# Pyr0-Piezo-Standalone_3_0_0.net
KiCad netlist of a schematic drawn in EAGLE
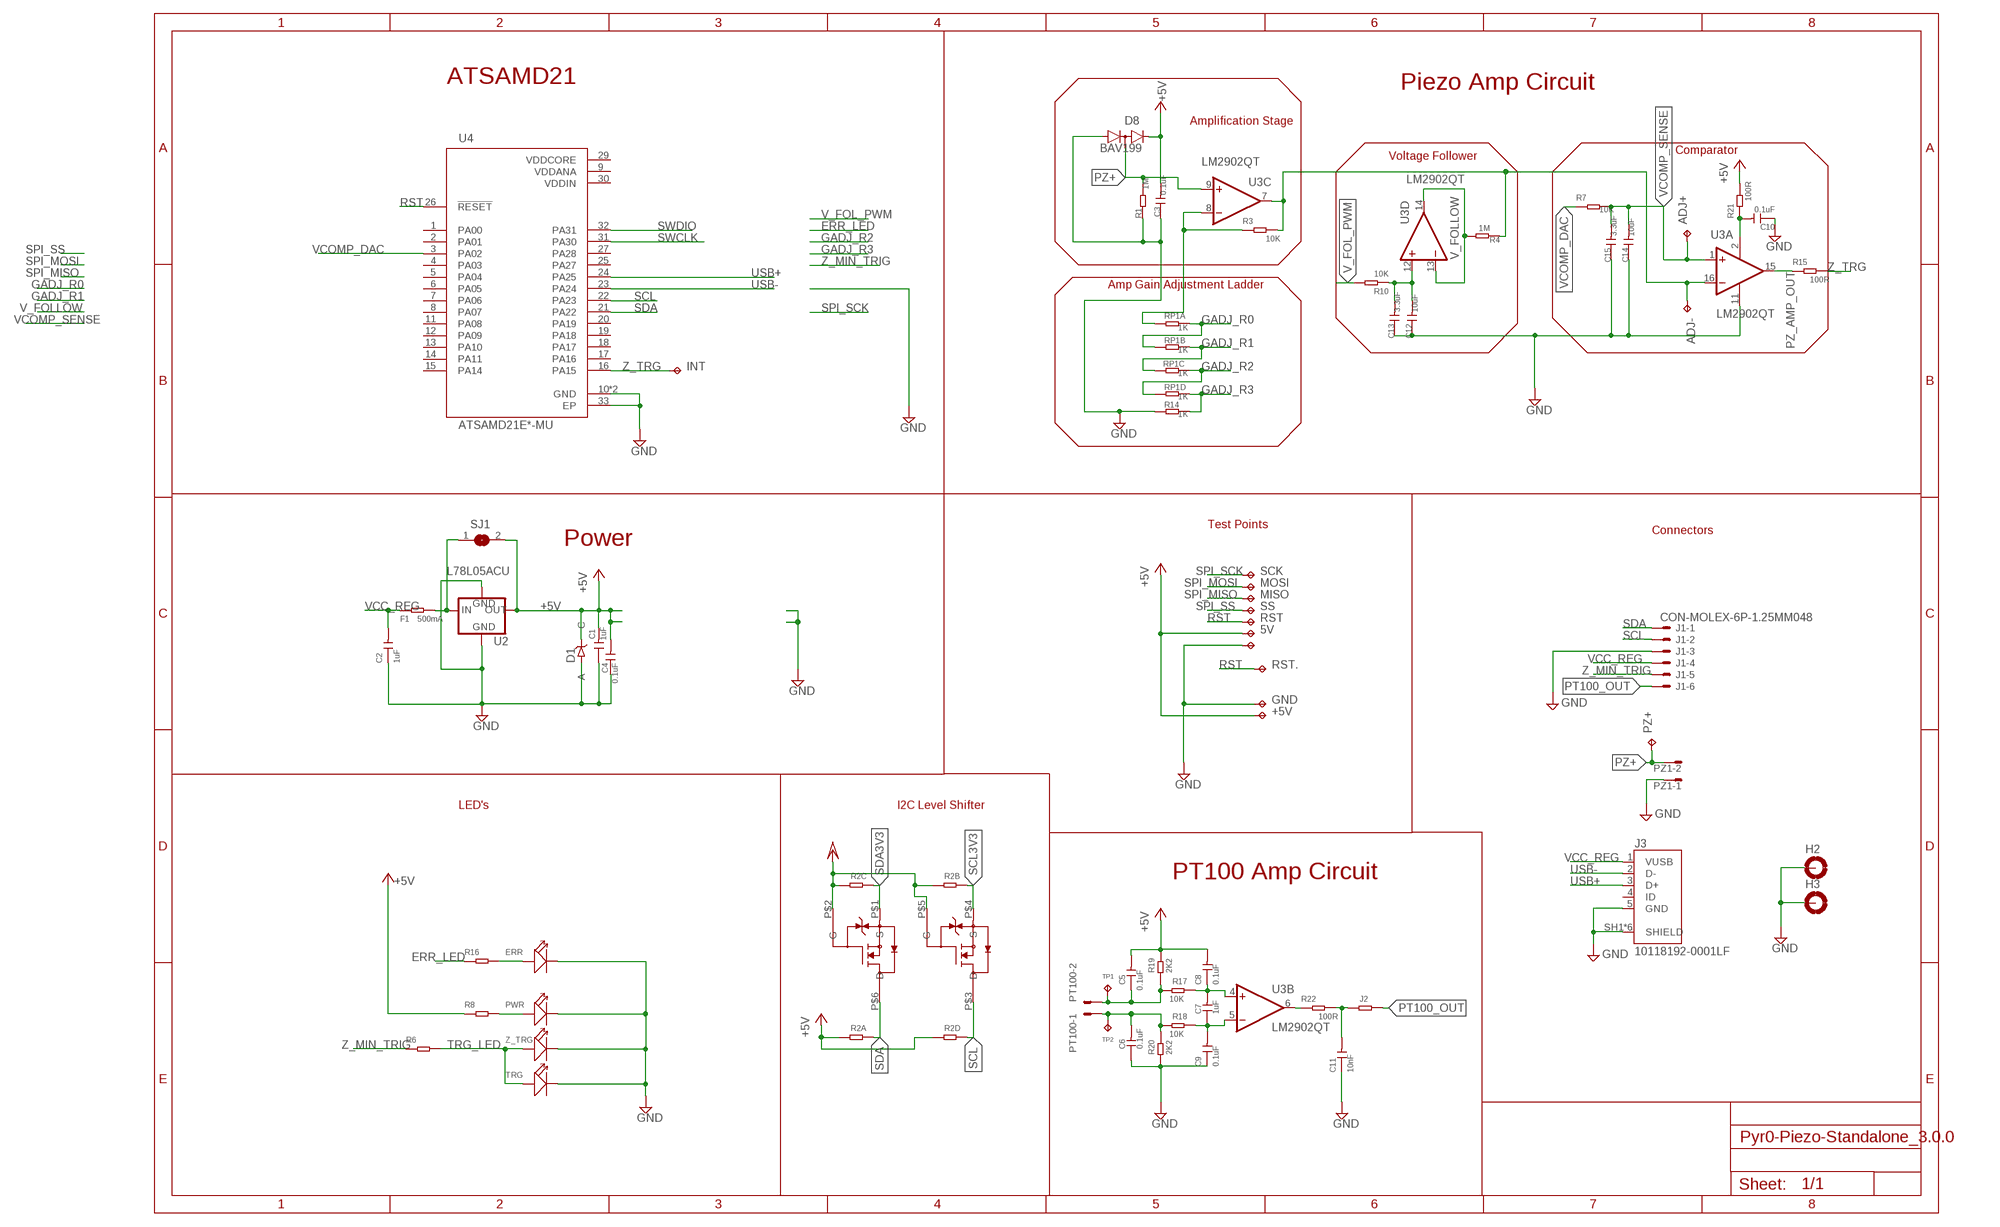
[diagram p0: schematic, sheet 1]

(export (version "E")
  (design (tool "Eeschema 10.0.6"))
  (components
    (comp (ref "+5V")
      (value "TPTP13SQ")
      (footprint "eagle-import:TP13SQ")
      (libsource (lib "eagle-import") (part "testpad_385_TPTP13SQ"))
    )
    (comp (ref "5V")
      (value "TPTP13SQ")
      (footprint "eagle-import:TP13SQ")
      (libsource (lib "eagle-import") (part "TPTP13SQ"))
    )
    (comp (ref "ADJ+")
      (value "TPTP13SQ")
      (footprint "eagle-import:TP13SQ")
      (libsource (lib "eagle-import") (part "TPTP13SQ"))
    )
    (comp (ref "ADJ-")
      (value "TPTP13SQ")
      (footprint "eagle-import:TP13SQ")
      (libsource (lib "eagle-import") (part "TPTP13SQ"))
    )
    (comp (ref "C1")
      (value "1uF")
      (footprint "eagle-import:CAPC1609X80")
      (libsource (lib "eagle-import") (part "SEEED-CAPACITOR_CERAMIC-10UF-25V-10%-X5R(0805)CAP_0603_GEN"))
    )
    (comp (ref "C2")
      (value "1uF")
      (footprint "eagle-import:CAPC1609X80")
      (libsource (lib "eagle-import") (part "SEEED-CAPACITOR_CERAMIC-10UF-25V-10%-X5R(0805)CAP_0603_GEN"))
    )
    (comp (ref "C3")
      (value "0.1uF")
      (footprint "eagle-import:CAPC1005X50")
      (libsource (lib "eagle-import") (part "CERAMIC-1NF-50V-10%-X7R(0402)CAP_0402"))
    )
    (comp (ref "C4")
      (value "0.1uF")
      (footprint "eagle-import:CAPC1005X50")
      (libsource (lib "eagle-import") (part "CERAMIC-1NF-50V-10%-X7R(0402)CAP_0402"))
    )
    (comp (ref "C5")
      (value "0.1uF")
      (footprint "eagle-import:CAPC1005X50")
      (libsource (lib "eagle-import") (part "CERAMIC-1NF-50V-10%-X7R(0402)CAP_0402"))
    )
    (comp (ref "C6")
      (value "0.1uF")
      (footprint "eagle-import:CAPC1005X50")
      (libsource (lib "eagle-import") (part "CERAMIC-1NF-50V-10%-X7R(0402)CAP_0402"))
    )
    (comp (ref "C7")
      (value "1uF")
      (footprint "eagle-import:CAPC1005X50")
      (libsource (lib "eagle-import") (part "CERAMIC-1NF-50V-10%-X7R(0402)CAP_0402"))
    )
    (comp (ref "C8")
      (value "0.1uF")
      (footprint "eagle-import:CAPC1005X50")
      (libsource (lib "eagle-import") (part "CERAMIC-1NF-50V-10%-X7R(0402)CAP_0402"))
    )
    (comp (ref "C9")
      (value "0.1uF")
      (footprint "eagle-import:CAPC1005X50")
      (libsource (lib "eagle-import") (part "CERAMIC-1NF-50V-10%-X7R(0402)CAP_0402"))
    )
    (comp (ref "C10")
      (value "0.1uF")
      (footprint "eagle-import:CAPC1005X50")
      (libsource (lib "eagle-import") (part "CERAMIC-1NF-50V-10%-X7R(0402)CAP_0402"))
    )
    (comp (ref "C11")
      (value "10nF")
      (footprint "eagle-import:CAPC1005X50")
      (libsource (lib "eagle-import") (part "CERAMIC-1NF-50V-10%-X7R(0402)CAP_0402"))
    )
    (comp (ref "C12")
      (value "10uF")
      (footprint "eagle-import:CAPC1005X50")
      (libsource (lib "eagle-import") (part "CERAMIC-1NF-50V-10%-X7R(0402)CAP_0402"))
    )
    (comp (ref "C13")
      (value "3.3uF")
      (footprint "eagle-import:CAPC1005X50")
      (libsource (lib "eagle-import") (part "CERAMIC-1NF-50V-10%-X7R(0402)CAP_0402"))
    )
    (comp (ref "C14")
      (value "10uF")
      (footprint "eagle-import:CAPC1005X50")
      (libsource (lib "eagle-import") (part "CERAMIC-1NF-50V-10%-X7R(0402)CAP_0402"))
    )
    (comp (ref "C15")
      (value "3.3uF")
      (footprint "eagle-import:CAPC1005X50")
      (libsource (lib "eagle-import") (part "CERAMIC-1NF-50V-10%-X7R(0402)CAP_0402"))
    )
    (comp (ref "D1")
      (value "ZENER_DIODE_PLZ5V1C")
      (footprint "eagle-import:DO-219AC")
      (libsource (lib "eagle-import") (part "ZENER_DIODE_PLZ5V1C"))
    )
    (comp (ref "D8")
      (value "BAV199")
      (footprint "eagle-import:SOT23")
      (libsource (lib "eagle-import") (part "BAV199"))
    )
    (comp (ref "ERR")
      (value "SEEED-LED_SMD-LED-CLEAR-BLUE(0603)LED_0603")
      (footprint "eagle-import:SEEED-LED_LED-0603")
      (libsource (lib "eagle-import") (part "SEEED-LED_SMD-LED-CLEAR-BLUE(0603)LED_0603"))
    )
    (comp (ref "F1")
      (value "500mA")
      (footprint "eagle-import:R0402")
      (fields (field (name "MPN") "RC0402JR-070RL"))
      (libsource (lib "eagle-import") (part "SMD-RES-0R-5%-1/16W(0402)"))
    )
    (comp (ref "GND")
      (value "TPTP13SQ")
      (footprint "eagle-import:TP13SQ")
      (libsource (lib "eagle-import") (part "testpad_385_TPTP13SQ"))
    )
    (comp (ref "H2")
      (value "HOLES_MOUNT-PAD-ROUND2.8")
      (footprint "eagle-import:HOLES_2,8-PAD")
      (libsource (lib "eagle-import") (part "HOLES_MOUNT-PAD-ROUND2.8"))
    )
    (comp (ref "H3")
      (value "HOLES_MOUNT-PAD-ROUND2.8")
      (footprint "eagle-import:HOLES_2,8-PAD")
      (libsource (lib "eagle-import") (part "HOLES_MOUNT-PAD-ROUND2.8"))
    )
    (comp (ref "INT")
      (value "TPTP06R")
      (footprint "eagle-import:TP06R")
      (libsource (lib "eagle-import") (part "testpad_385_TPTP06R"))
    )
    (comp (ref "J1")
      (value "CON-MOLEX-6P-1.25MM048")
      (footprint "eagle-import:53048-06")
      (fields (field (name "MF") "WALDOM/MOLEX") (field (name "MPN") "53048-0610"))
      (libsource (lib "eagle-import") (part "CON-MOLEX-6P-1.25MM048"))
    )
    (comp (ref "J2")
      (value "SEEED-RESISTOR_SMD-RES-1.5K-1%-1/10W(0603)DETAILED_MODEL")
      (footprint "eagle-import:SEEED-RESISTOR_R0603")
      (libsource (lib "eagle-import") (part "SEEED-RESISTOR_SMD-RES-1.5K-1%-1/10W(0603)DETAILED_MODEL"))
    )
    (comp (ref "J3")
      (value "10118192-0001LF")
      (footprint "eagle-import:AMPHENOL_10118192-0001LF")
      (fields (field (name "DIGI-KEY_PART_NUMBER") "609-4613-1-ND") (field (name "MF") "Amphenol FCI"))
      (libsource (lib "eagle-import") (part "10118192-0001LF"))
    )
    (comp (ref "MISO")
      (value "TPTP13SQ")
      (footprint "eagle-import:TP13SQ")
      (libsource (lib "eagle-import") (part "TPTP13SQ"))
    )
    (comp (ref "MOSI")
      (value "TPTP13SQ")
      (footprint "eagle-import:TP13SQ")
      (libsource (lib "eagle-import") (part "TPTP13SQ"))
    )
    (comp (ref "PT100")
      (value "CON-MOLEX-2P-1.27MM048")
      (footprint "eagle-import:53048-02")
      (fields (field (name "MF") "MOLEX") (field (name "MPN") "53048-0210"))
      (libsource (lib "eagle-import") (part "CON-MOLEX-2P-1.27MM048"))
    )
    (comp (ref "PWR")
      (value "SEEED-LED_SMD-LED-CLEAR-BLUE(0603)LED_0603")
      (footprint "eagle-import:SEEED-LED_LED-0603")
      (libsource (lib "eagle-import") (part "SEEED-LED_SMD-LED-CLEAR-BLUE(0603)LED_0603"))
    )
    (comp (ref "PZ+")
      (value "TPTP13SQ")
      (footprint "eagle-import:TP13SQ")
      (libsource (lib "eagle-import") (part "TPTP13SQ"))
    )
    (comp (ref "PZ1")
      (value "CON-MOLEX-2P-1.27MM048")
      (footprint "eagle-import:53048-02")
      (fields (field (name "MF") "MOLEX") (field (name "MPN") "53048-0210"))
      (libsource (lib "eagle-import") (part "CON-MOLEX-2P-1.27MM048"))
    )
    (comp (ref "R1")
      (value "1M")
      (footprint "eagle-import:R0402")
      (fields (field (name "MPN") "RC0402JR-070RL"))
      (libsource (lib "eagle-import") (part "SMD-RES-0R-5%-1/16W(0402)"))
    )
    (comp (ref "R2")
      (value "RESISTOR_NETWORK_X40804_L")
      (footprint "eagle-import:EXBN8V-L")
      (libsource (lib "eagle-import") (part "RESISTOR_NETWORK_X40804_L"))
    )
    (comp (ref "R3")
      (value "10K")
      (footprint "eagle-import:R0402")
      (fields (field (name "MPN") "RC0402JR-070RL"))
      (libsource (lib "eagle-import") (part "SMD-RES-0R-5%-1/16W(0402)"))
    )
    (comp (ref "R4")
      (value "1M")
      (footprint "eagle-import:R0402")
      (fields (field (name "MPN") "RC0402JR-070RL"))
      (libsource (lib "eagle-import") (part "SMD-RES-0R-5%-1/16W(0402)"))
    )
    (comp (ref "R6")
      (value "SMD-RES-0R-5%-1/16W(0402)")
      (footprint "eagle-import:R0402")
      (fields (field (name "MPN") "RC0402JR-070RL"))
      (libsource (lib "eagle-import") (part "SMD-RES-0R-5%-1/16W(0402)"))
    )
    (comp (ref "R7")
      (value "10K")
      (footprint "eagle-import:R0402")
      (fields (field (name "MPN") "RC0402JR-070RL"))
      (libsource (lib "eagle-import") (part "SMD-RES-0R-5%-1/16W(0402)"))
    )
    (comp (ref "R8")
      (value "SMD-RES-0R-5%-1/16W(0402)")
      (footprint "eagle-import:R0402")
      (fields (field (name "MPN") "RC0402JR-070RL"))
      (libsource (lib "eagle-import") (part "SMD-RES-0R-5%-1/16W(0402)"))
    )
    (comp (ref "R10")
      (value "10K")
      (footprint "eagle-import:R0402")
      (fields (field (name "MPN") "RC0402JR-070RL"))
      (libsource (lib "eagle-import") (part "SMD-RES-0R-5%-1/16W(0402)"))
    )
    (comp (ref "R14")
      (value "1K")
      (footprint "eagle-import:R0402")
      (fields (field (name "MPN") "RC0402JR-070RL"))
      (libsource (lib "eagle-import") (part "SMD-RES-0R-5%-1/16W(0402)"))
    )
    (comp (ref "R15")
      (value "100R")
      (footprint "eagle-import:R0402")
      (fields (field (name "MPN") "RC0402JR-070RL"))
      (libsource (lib "eagle-import") (part "SMD-RES-0R-5%-1/16W(0402)"))
    )
    (comp (ref "R16")
      (value "SMD-RES-0R-5%-1/16W(0402)")
      (footprint "eagle-import:R0402")
      (fields (field (name "MPN") "RC0402JR-070RL"))
      (libsource (lib "eagle-import") (part "SMD-RES-0R-5%-1/16W(0402)"))
    )
    (comp (ref "R17")
      (value "10K")
      (footprint "eagle-import:R0402")
      (fields (field (name "MPN") "RC0402JR-070RL"))
      (libsource (lib "eagle-import") (part "SMD-RES-0R-5%-1/16W(0402)"))
    )
    (comp (ref "R18")
      (value "10K")
      (footprint "eagle-import:R0402")
      (fields (field (name "MPN") "RC0402JR-070RL"))
      (libsource (lib "eagle-import") (part "SMD-RES-0R-5%-1/16W(0402)"))
    )
    (comp (ref "R19")
      (value "2K2")
      (footprint "eagle-import:R0402")
      (fields (field (name "MPN") "RC0402JR-070RL"))
      (libsource (lib "eagle-import") (part "SMD-RES-0R-5%-1/16W(0402)"))
    )
    (comp (ref "R20")
      (value "2K2")
      (footprint "eagle-import:R0402")
      (fields (field (name "MPN") "RC0402JR-070RL"))
      (libsource (lib "eagle-import") (part "SMD-RES-0R-5%-1/16W(0402)"))
    )
    (comp (ref "R21")
      (value "100R")
      (footprint "eagle-import:R0402")
      (fields (field (name "MPN") "RC0402JR-070RL"))
      (libsource (lib "eagle-import") (part "SMD-RES-0R-5%-1/16W(0402)"))
    )
    (comp (ref "R22")
      (value "100R")
      (footprint "eagle-import:R0402")
      (fields (field (name "MPN") "RC0402JR-070RL"))
      (libsource (lib "eagle-import") (part "SMD-RES-0R-5%-1/16W(0402)"))
    )
    (comp (ref "RP1")
      (value "1K")
      (footprint "eagle-import:EXBN8V-L")
      (libsource (lib "eagle-import") (part "RESISTOR_NETWORK_X40804_L"))
    )
    (comp (ref "RST")
      (value "TPTP13SQ")
      (footprint "eagle-import:TP13SQ")
      (libsource (lib "eagle-import") (part "TPTP13SQ"))
    )
    (comp (ref "RST.")
      (value "TPTP13SQ")
      (footprint "eagle-import:TP13SQ")
      (libsource (lib "eagle-import") (part "testpad_385_TPTP13SQ"))
    )
    (comp (ref "SCK")
      (value "TPTP13SQ")
      (footprint "eagle-import:TP13SQ")
      (libsource (lib "eagle-import") (part "TPTP13SQ"))
    )
    (comp (ref "SJ1")
      (value "SJM")
      (footprint "eagle-import:SJM")
      (libsource (lib "eagle-import") (part "SJM"))
    )
    (comp (ref "SS")
      (value "TPTP06R")
      (footprint "eagle-import:TP06R")
      (libsource (lib "eagle-import") (part "testpad_385_TPTP06R"))
    )
    (comp (ref "TP1")
      (value "TPTP09R")
      (footprint "eagle-import:TP09R")
      (libsource (lib "eagle-import") (part "TPTP09R"))
    )
    (comp (ref "TP2")
      (value "TPTP09R")
      (footprint "eagle-import:TP09R")
      (libsource (lib "eagle-import") (part "TPTP09R"))
    )
    (comp (ref "TRG")
      (value "SEEED-LED_SMD-LED-CLEAR-BLUE(0603)LED_0603")
      (footprint "eagle-import:SEEED-LED_LED-0603")
      (libsource (lib "eagle-import") (part "SEEED-LED_SMD-LED-CLEAR-BLUE(0603)LED_0603"))
    )
    (comp (ref "U$3")
      (value "MOSFET_ARRAY_EMK34")
      (footprint "eagle-import:SOT-563")
      (libsource (lib "eagle-import") (part "MOSFET_ARRAY_EMK34"))
    )
    (comp (ref "U2")
      (value "L78L05ACU")
      (footprint "eagle-import:SOT89")
      (fields (field (name "MF") "STMicroelectronics") (field (name "MP") "L78L05ACU-TR"))
      (libsource (lib "eagle-import") (part "L78L05ACU"))
    )
    (comp (ref "U3")
      (value "LM2902QT")
      (footprint "eagle-import:QFN16")
      (libsource (lib "eagle-import") (part "LM2902QT"))
    )
    (comp (ref "U4")
      (value "ATSAMD21E*-MU")
      (footprint "eagle-import:QFN50P500X500X100-33N")
      (fields (field (name "MF") "Microchip") (field (name "MP") "ATSAMD21E18A-MU"))
      (libsource (lib "eagle-import") (part "ATSAMD21E-MU"))
    )
    (comp (ref "Z_TRG")
      (value "SEEED-LED_SMD-LED-CLEAR-BLUE(0603)LED_0603")
      (footprint "eagle-import:SEEED-LED_LED-0603")
      (libsource (lib "eagle-import") (part "SEEED-LED_SMD-LED-CLEAR-BLUE(0603)LED_0603"))
    )
    (comp (ref "⏚")
      (value "TPTP13SQ")
      (footprint "eagle-import:TP13SQ")
      (libsource (lib "eagle-import") (part "testpad_385_TPTP13SQ"))
    )
  )
  (nets
    (net (code "1") (name "+3.3V") (class "Default")
      (node (ref "R2") (pin "6") (pinfunction "2_6") (pintype "passive"))
      (node (ref "R2") (pin "7") (pinfunction "2_7") (pintype "passive"))
      (node (ref "U$3") (pin "P$2") (pinfunction "G_P$2") (pintype "bidirectional"))
      (node (ref "U$3") (pin "P$5") (pinfunction "G_P$5") (pintype "bidirectional"))
    )
    (net (code "2") (name "+5V") (class "Default")
      (node (ref "+5V") (pin "TP") (pinfunction "TP_TP") (pintype "input"))
      (node (ref "5V") (pin "TP") (pinfunction "TP_TP") (pintype "input"))
      (node (ref "C1") (pin "2") (pinfunction "2_2") (pintype "passive"))
      (node (ref "C3") (pin "2") (pinfunction "2_2") (pintype "passive"))
      (node (ref "C4") (pin "2") (pinfunction "2_2") (pintype "passive"))
      (node (ref "C5") (pin "2") (pinfunction "2_2") (pintype "passive"))
      (node (ref "C8") (pin "2") (pinfunction "2_2") (pintype "passive"))
      (node (ref "D1") (pin "P$2") (pinfunction "C_P$2") (pintype "passive"))
      (node (ref "D8") (pin "2") (pinfunction "C_2") (pintype "passive"))
      (node (ref "R19") (pin "2") (pinfunction "2_2") (pintype "passive"))
      (node (ref "R2") (pin "5") (pinfunction "2_5") (pintype "passive"))
      (node (ref "R2") (pin "8") (pinfunction "2_8") (pintype "passive"))
      (node (ref "R21") (pin "2") (pinfunction "2_2") (pintype "passive"))
      (node (ref "R8") (pin "1") (pinfunction "1_1") (pintype "passive"))
      (node (ref "SJ1") (pin "2") (pinfunction "2_2") (pintype "passive"))
      (node (ref "U2") (pin "1") (pinfunction "OUT_1") (pintype "output"))
    )
    (net (code "3") (name "/ERR_LED") (class "Default")
      (node (ref "R16") (pin "1") (pinfunction "1_1") (pintype "passive"))
    )
    (net (code "4") (name "/GADJ_R0") (class "Default")
      (node (ref "RP1") (pin "2") (pinfunction "1_2") (pintype "passive"))
      (node (ref "RP1") (pin "8") (pinfunction "2_8") (pintype "passive"))
    )
    (net (code "5") (name "/GADJ_R1") (class "Default")
      (node (ref "RP1") (pin "3") (pinfunction "1_3") (pintype "passive"))
      (node (ref "RP1") (pin "7") (pinfunction "2_7") (pintype "passive"))
    )
    (net (code "6") (name "/GADJ_R2") (class "Default")
      (node (ref "RP1") (pin "4") (pinfunction "1_4") (pintype "passive"))
      (node (ref "RP1") (pin "6") (pinfunction "2_6") (pintype "passive"))
    )
    (net (code "7") (name "/GADJ_R3") (class "Default")
      (node (ref "R14") (pin "2") (pinfunction "2_2") (pintype "passive"))
      (node (ref "RP1") (pin "5") (pinfunction "2_5") (pintype "passive"))
    )
    (net (code "8") (name "/PZ_AMP_OUT") (class "Default")
      (node (ref "R15") (pin "1") (pinfunction "1_1") (pintype "passive"))
      (node (ref "U3") (pin "15") (pinfunction "OUT_15") (pintype "output"))
    )
    (net (code "9") (name "/RST") (class "Default")
      (node (ref "RST") (pin "TP") (pinfunction "TP_TP") (pintype "input"))
      (node (ref "RST.") (pin "TP") (pinfunction "TP_TP") (pintype "input"))
      (node (ref "U4") (pin "26") (pinfunction "~{RESET}_26") (pintype "input"))
    )
    (net (code "10") (name "/SPI_MISO") (class "Default")
      (node (ref "MISO") (pin "TP") (pinfunction "TP_TP") (pintype "input"))
    )
    (net (code "11") (name "/SPI_MOSI") (class "Default")
      (node (ref "MOSI") (pin "TP") (pinfunction "TP_TP") (pintype "input"))
    )
    (net (code "12") (name "/SPI_SCK") (class "Default")
      (node (ref "SCK") (pin "TP") (pinfunction "TP_TP") (pintype "input"))
    )
    (net (code "13") (name "/SPI_SS") (class "Default")
      (node (ref "SS") (pin "TP") (pinfunction "TP_TP") (pintype "input"))
    )
    (net (code "14") (name "/SWCLK") (class "Default")
      (node (ref "U4") (pin "31") (pinfunction "PA30_31") (pintype "bidirectional"))
    )
    (net (code "15") (name "/SWDIO") (class "Default")
      (node (ref "U4") (pin "32") (pinfunction "PA31_32") (pintype "bidirectional"))
    )
    (net (code "16") (name "/TRG_LED") (class "Default")
      (node (ref "R6") (pin "2") (pinfunction "2_2") (pintype "passive"))
      (node (ref "TRG") (pin "+") (pinfunction "+_+") (pintype "passive"))
      (node (ref "Z_TRG") (pin "+") (pinfunction "+_+") (pintype "passive"))
    )
    (net (code "17") (name "/USB+") (class "Default")
      (node (ref "J3") (pin "3") (pinfunction "D+_3") (pintype "passive"))
      (node (ref "U4") (pin "24") (pinfunction "PA25_24") (pintype "bidirectional"))
    )
    (net (code "18") (name "/USB-") (class "Default")
      (node (ref "J3") (pin "2") (pinfunction "D-_2") (pintype "passive"))
      (node (ref "U4") (pin "23") (pinfunction "PA24_23") (pintype "bidirectional"))
    )
    (net (code "19") (name "/VCC_REG") (class "Default")
      (node (ref "C2") (pin "2") (pinfunction "2_2") (pintype "passive"))
      (node (ref "F1") (pin "1") (pinfunction "1_1") (pintype "passive"))
      (node (ref "J1") (pin "4") (pinfunction "S_4") (pintype "passive"))
      (node (ref "J3") (pin "1") (pinfunction "VUSB_1") (pintype "passive"))
    )
    (net (code "20") (name "/VDDANA") (class "Default")
      (node (ref "U4") (pin "9") (pinfunction "VDDANA_9") (pintype "power_in"))
    )
    (net (code "21") (name "/VDDCORE") (class "Default")
      (node (ref "U4") (pin "29") (pinfunction "VDDCORE_29") (pintype "power_in"))
    )
    (net (code "22") (name "/VDDIN") (class "Default")
      (node (ref "U4") (pin "30") (pinfunction "VDDIN_30") (pintype "power_in"))
    )
    (net (code "23") (name "/V_FOLLOW") (class "Default")
      (node (ref "R4") (pin "2") (pinfunction "2_2") (pintype "passive"))
      (node (ref "U3") (pin "13") (pinfunction "-IN_13") (pintype "input"))
      (node (ref "U3") (pin "14") (pinfunction "OUT_14") (pintype "output"))
    )
    (net (code "24") (name "/Z_MIN_TRIG") (class "Default")
      (node (ref "J1") (pin "5") (pinfunction "S_5") (pintype "passive"))
      (node (ref "R6") (pin "1") (pinfunction "1_1") (pintype "passive"))
    )
    (net (code "25") (name "/Z_TRG") (class "Default")
      (node (ref "INT") (pin "TP") (pinfunction "TP_TP") (pintype "input"))
      (node (ref "R15") (pin "2") (pinfunction "2_2") (pintype "passive"))
      (node (ref "U4") (pin "16") (pinfunction "PA15_16") (pintype "bidirectional"))
    )
    (net (code "26") (name "GND") (class "Default")
      (node (ref "C1") (pin "1") (pinfunction "1_1") (pintype "passive"))
      (node (ref "C10") (pin "1") (pinfunction "1_1") (pintype "passive"))
      (node (ref "C11") (pin "1") (pinfunction "1_1") (pintype "passive"))
      (node (ref "C12") (pin "1") (pinfunction "1_1") (pintype "passive"))
      (node (ref "C13") (pin "1") (pinfunction "1_1") (pintype "passive"))
      (node (ref "C14") (pin "1") (pinfunction "1_1") (pintype "passive"))
      (node (ref "C15") (pin "1") (pinfunction "1_1") (pintype "passive"))
      (node (ref "C2") (pin "1") (pinfunction "1_1") (pintype "passive"))
      (node (ref "C3") (pin "1") (pinfunction "1_1") (pintype "passive"))
      (node (ref "C4") (pin "1") (pinfunction "1_1") (pintype "passive"))
      (node (ref "C6") (pin "1") (pinfunction "1_1") (pintype "passive"))
      (node (ref "C9") (pin "1") (pinfunction "1_1") (pintype "passive"))
      (node (ref "D1") (pin "P$1") (pinfunction "A_P$1") (pintype "passive"))
      (node (ref "D8") (pin "1") (pinfunction "A_1") (pintype "passive"))
      (node (ref "ERR") (pin "-") (pinfunction "-_-") (pintype "passive"))
      (node (ref "GND") (pin "TP") (pinfunction "TP_TP") (pintype "input"))
      (node (ref "H2") (pin "B2,8") (pinfunction "MOUNT_B2,8") (pintype "passive"))
      (node (ref "H3") (pin "B2,8") (pinfunction "MOUNT_B2,8") (pintype "passive"))
      (node (ref "J1") (pin "3") (pinfunction "S_3") (pintype "passive"))
      (node (ref "J3") (pin "5") (pinfunction "GND_5") (pintype "passive"))
      (node (ref "J3") (pin "SH1") (pinfunction "SHIELD_SH1") (pintype "passive"))
      (node (ref "J3") (pin "SH2") (pinfunction "SHIELD_SH2") (pintype "passive"))
      (node (ref "J3") (pin "SH3") (pinfunction "SHIELD_SH3") (pintype "passive"))
      (node (ref "J3") (pin "SH4") (pinfunction "SHIELD_SH4") (pintype "passive"))
      (node (ref "J3") (pin "SH5") (pinfunction "SHIELD_SH5") (pintype "passive"))
      (node (ref "J3") (pin "SH6") (pinfunction "SHIELD_SH6") (pintype "passive"))
      (node (ref "PWR") (pin "-") (pinfunction "-_-") (pintype "passive"))
      (node (ref "PZ1") (pin "1") (pinfunction "S_1") (pintype "passive"))
      (node (ref "R1") (pin "1") (pinfunction "1_1") (pintype "passive"))
      (node (ref "R14") (pin "1") (pinfunction "1_1") (pintype "passive"))
      (node (ref "R20") (pin "1") (pinfunction "1_1") (pintype "passive"))
      (node (ref "TRG") (pin "-") (pinfunction "-_-") (pintype "passive"))
      (node (ref "U2") (pin "2") (pinfunction "GND_2") (pintype "power_in"))
      (node (ref "U2") (pin "PAD") (pinfunction "PAD_PAD") (pintype "power_in"))
      (node (ref "U3") (pin "11") (pinfunction "V-_11") (pintype "power_in"))
      (node (ref "U4") (pin "10") (pinfunction "GND_10") (pintype "power_in"))
      (node (ref "U4") (pin "28") (pinfunction "GND_28") (pintype "power_in"))
      (node (ref "U4") (pin "33") (pinfunction "EP_33") (pintype "power_in"))
      (node (ref "Z_TRG") (pin "-") (pinfunction "-_-") (pintype "passive"))
      (node (ref "⏚") (pin "TP") (pinfunction "TP_TP") (pintype "input"))
    )
    (net (code "27") (name "Net-(C11-Pad2)") (class "Default")
      (node (ref "C11") (pin "2") (pinfunction "2_2") (pintype "passive"))
      (node (ref "J2") (pin "1") (pinfunction "1_1") (pintype "passive"))
      (node (ref "R22") (pin "2") (pinfunction "2_2") (pintype "passive"))
    )
    (net (code "28") (name "Net-(ERR-Pad+)") (class "Default")
      (node (ref "ERR") (pin "+") (pinfunction "+_+") (pintype "passive"))
      (node (ref "R16") (pin "2") (pinfunction "2_2") (pintype "passive"))
    )
    (net (code "29") (name "Net-(PT100A-S)") (class "Default")
      (node (ref "C6") (pin "2") (pinfunction "2_2") (pintype "passive"))
      (node (ref "PT100") (pin "1") (pinfunction "S_1") (pintype "passive"))
      (node (ref "R18") (pin "1") (pinfunction "1_1") (pintype "passive"))
      (node (ref "R20") (pin "2") (pinfunction "2_2") (pintype "passive"))
      (node (ref "TP2") (pin "TP") (pinfunction "TP_TP") (pintype "input"))
    )
    (net (code "30") (name "Net-(PT100B-S)") (class "Default")
      (node (ref "C5") (pin "1") (pinfunction "1_1") (pintype "passive"))
      (node (ref "PT100") (pin "2") (pinfunction "S_2") (pintype "passive"))
      (node (ref "R17") (pin "1") (pinfunction "1_1") (pintype "passive"))
      (node (ref "R19") (pin "1") (pinfunction "1_1") (pintype "passive"))
      (node (ref "TP1") (pin "TP") (pinfunction "TP_TP") (pintype "input"))
    )
    (net (code "31") (name "Net-(PWR-Pad+)") (class "Default")
      (node (ref "PWR") (pin "+") (pinfunction "+_+") (pintype "passive"))
      (node (ref "R8") (pin "2") (pinfunction "2_2") (pintype "passive"))
    )
    (net (code "32") (name "Net-(U2-IN)") (class "Default")
      (node (ref "F1") (pin "2") (pinfunction "2_2") (pintype "passive"))
      (node (ref "SJ1") (pin "1") (pinfunction "1_1") (pintype "passive"))
      (node (ref "U2") (pin "3") (pinfunction "IN_3") (pintype "input"))
    )
    (net (code "33") (name "Net-(U3A--IN)") (class "Default")
      (node (ref "ADJ-") (pin "TP") (pinfunction "TP_TP") (pintype "input"))
      (node (ref "R3") (pin "2") (pinfunction "2_2") (pintype "passive"))
      (node (ref "R4") (pin "1") (pinfunction "1_1") (pintype "passive"))
      (node (ref "U3") (pin "16") (pinfunction "-IN_16") (pintype "input"))
      (node (ref "U3") (pin "7") (pinfunction "OUT_7") (pintype "output"))
    )
    (net (code "34") (name "Net-(U3B-+IN)") (class "Default")
      (node (ref "C7") (pin "2") (pinfunction "2_2") (pintype "passive"))
      (node (ref "C8") (pin "1") (pinfunction "1_1") (pintype "passive"))
      (node (ref "R17") (pin "2") (pinfunction "2_2") (pintype "passive"))
      (node (ref "U3") (pin "4") (pinfunction "+IN_4") (pintype "input"))
    )
    (net (code "35") (name "Net-(U3B--IN)") (class "Default")
      (node (ref "C7") (pin "1") (pinfunction "1_1") (pintype "passive"))
      (node (ref "C9") (pin "2") (pinfunction "2_2") (pintype "passive"))
      (node (ref "R18") (pin "2") (pinfunction "2_2") (pintype "passive"))
      (node (ref "U3") (pin "5") (pinfunction "-IN_5") (pintype "input"))
    )
    (net (code "36") (name "Net-(U3B-OUT)") (class "Default")
      (node (ref "R22") (pin "1") (pinfunction "1_1") (pintype "passive"))
      (node (ref "U3") (pin "6") (pinfunction "OUT_6") (pintype "output"))
    )
    (net (code "37") (name "Net-(U3C--IN)") (class "Default")
      (node (ref "R3") (pin "1") (pinfunction "1_1") (pintype "passive"))
      (node (ref "RP1") (pin "1") (pinfunction "1_1") (pintype "passive"))
      (node (ref "U3") (pin "8") (pinfunction "-IN_8") (pintype "input"))
    )
    (net (code "38") (name "Net-(U3D-+IN)") (class "Default")
      (node (ref "C12") (pin "2") (pinfunction "2_2") (pintype "passive"))
      (node (ref "C13") (pin "2") (pinfunction "2_2") (pintype "passive"))
      (node (ref "R10") (pin "1") (pinfunction "1_1") (pintype "passive"))
      (node (ref "U3") (pin "12") (pinfunction "+IN_12") (pintype "input"))
    )
    (net (code "39") (name "Net-(U3E-V+)") (class "Default")
      (node (ref "C10") (pin "2") (pinfunction "2_2") (pintype "passive"))
      (node (ref "R21") (pin "1") (pinfunction "1_1") (pintype "passive"))
      (node (ref "U3") (pin "2") (pinfunction "V+_2") (pintype "power_in"))
    )
    (net (code "40") (name "PT100_OUT") (class "Default")
      (node (ref "J1") (pin "6") (pinfunction "S_6") (pintype "passive"))
      (node (ref "J2") (pin "2") (pinfunction "2_2") (pintype "passive"))
    )
    (net (code "41") (name "PZ+") (class "Default")
      (node (ref "D8") (pin "3") (pinfunction "AC_3") (pintype "passive"))
      (node (ref "PZ+") (pin "TP") (pinfunction "TP_TP") (pintype "input"))
      (node (ref "PZ1") (pin "2") (pinfunction "S_2") (pintype "passive"))
      (node (ref "R1") (pin "2") (pinfunction "2_2") (pintype "passive"))
      (node (ref "U3") (pin "9") (pinfunction "+IN_9") (pintype "input"))
    )
    (net (code "42") (name "SCL") (class "Default")
      (node (ref "J1") (pin "2") (pinfunction "S_2") (pintype "passive"))
      (node (ref "R2") (pin "4") (pinfunction "1_4") (pintype "passive"))
      (node (ref "U$3") (pin "P$3") (pinfunction "D_P$3") (pintype "bidirectional"))
      (node (ref "U4") (pin "22") (pinfunction "PA23_22") (pintype "bidirectional"))
    )
    (net (code "43") (name "SCL3V3") (class "Default")
      (node (ref "R2") (pin "2") (pinfunction "1_2") (pintype "passive"))
      (node (ref "U$3") (pin "P$4") (pinfunction "S_P$4") (pintype "bidirectional"))
    )
    (net (code "44") (name "SDA") (class "Default")
      (node (ref "J1") (pin "1") (pinfunction "S_1") (pintype "passive"))
      (node (ref "R2") (pin "1") (pinfunction "1_1") (pintype "passive"))
      (node (ref "U$3") (pin "P$6") (pinfunction "D_P$6") (pintype "bidirectional"))
      (node (ref "U4") (pin "21") (pinfunction "PA22_21") (pintype "bidirectional"))
    )
    (net (code "45") (name "SDA3V3") (class "Default")
      (node (ref "R2") (pin "3") (pinfunction "1_3") (pintype "passive"))
      (node (ref "U$3") (pin "P$1") (pinfunction "S_P$1") (pintype "bidirectional"))
    )
    (net (code "46") (name "VCOMP_DAC") (class "Default")
      (node (ref "R7") (pin "1") (pinfunction "1_1") (pintype "passive"))
      (node (ref "U4") (pin "3") (pinfunction "PA02_3") (pintype "bidirectional"))
    )
    (net (code "47") (name "VCOMP_SENSE") (class "Default")
      (node (ref "ADJ+") (pin "TP") (pinfunction "TP_TP") (pintype "input"))
      (node (ref "C14") (pin "2") (pinfunction "2_2") (pintype "passive"))
      (node (ref "C15") (pin "2") (pinfunction "2_2") (pintype "passive"))
      (node (ref "R7") (pin "2") (pinfunction "2_2") (pintype "passive"))
      (node (ref "U3") (pin "1") (pinfunction "+IN_1") (pintype "input"))
    )
    (net (code "48") (name "V_FOL_PWM") (class "Default")
      (node (ref "R10") (pin "2") (pinfunction "2_2") (pintype "passive"))
    )
    (net (code "49") (name "unconnected-(J3-ID-Pad4)") (class "Default")
      (node (ref "J3") (pin "4") (pinfunction "ID_4") (pintype "passive"))
    )
    (net (code "50") (name "unconnected-(U4-PA00-Pad1)") (class "Default")
      (node (ref "U4") (pin "1") (pinfunction "PA00_1") (pintype "bidirectional"))
    )
    (net (code "51") (name "unconnected-(U4-PA01-Pad2)") (class "Default")
      (node (ref "U4") (pin "2") (pinfunction "PA01_2") (pintype "bidirectional"))
    )
    (net (code "52") (name "unconnected-(U4-PA03-Pad4)") (class "Default")
      (node (ref "U4") (pin "4") (pinfunction "PA03_4") (pintype "bidirectional"))
    )
    (net (code "53") (name "unconnected-(U4-PA04-Pad5)") (class "Default")
      (node (ref "U4") (pin "5") (pinfunction "PA04_5") (pintype "bidirectional"))
    )
    (net (code "54") (name "unconnected-(U4-PA05-Pad6)") (class "Default")
      (node (ref "U4") (pin "6") (pinfunction "PA05_6") (pintype "bidirectional"))
    )
    (net (code "55") (name "unconnected-(U4-PA06-Pad7)") (class "Default")
      (node (ref "U4") (pin "7") (pinfunction "PA06_7") (pintype "bidirectional"))
    )
    (net (code "56") (name "unconnected-(U4-PA07-Pad8)") (class "Default")
      (node (ref "U4") (pin "8") (pinfunction "PA07_8") (pintype "bidirectional"))
    )
    (net (code "57") (name "unconnected-(U4-PA08-Pad11)") (class "Default")
      (node (ref "U4") (pin "11") (pinfunction "PA08_11") (pintype "bidirectional"))
    )
    (net (code "58") (name "unconnected-(U4-PA09-Pad12)") (class "Default")
      (node (ref "U4") (pin "12") (pinfunction "PA09_12") (pintype "bidirectional"))
    )
    (net (code "59") (name "unconnected-(U4-PA10-Pad13)") (class "Default")
      (node (ref "U4") (pin "13") (pinfunction "PA10_13") (pintype "bidirectional"))
    )
    (net (code "60") (name "unconnected-(U4-PA11-Pad14)") (class "Default")
      (node (ref "U4") (pin "14") (pinfunction "PA11_14") (pintype "bidirectional"))
    )
    (net (code "61") (name "unconnected-(U4-PA14-Pad15)") (class "Default")
      (node (ref "U4") (pin "15") (pinfunction "PA14_15") (pintype "bidirectional"))
    )
    (net (code "62") (name "unconnected-(U4-PA16-Pad17)") (class "Default")
      (node (ref "U4") (pin "17") (pinfunction "PA16_17") (pintype "bidirectional"))
    )
    (net (code "63") (name "unconnected-(U4-PA17-Pad18)") (class "Default")
      (node (ref "U4") (pin "18") (pinfunction "PA17_18") (pintype "bidirectional"))
    )
    (net (code "64") (name "unconnected-(U4-PA18-Pad19)") (class "Default")
      (node (ref "U4") (pin "19") (pinfunction "PA18_19") (pintype "bidirectional"))
    )
    (net (code "65") (name "unconnected-(U4-PA19-Pad20)") (class "Default")
      (node (ref "U4") (pin "20") (pinfunction "PA19_20") (pintype "bidirectional"))
    )
    (net (code "66") (name "unconnected-(U4-PA27-Pad25)") (class "Default")
      (node (ref "U4") (pin "25") (pinfunction "PA27_25") (pintype "bidirectional"))
    )
    (net (code "67") (name "unconnected-(U4-PA28-Pad27)") (class "Default")
      (node (ref "U4") (pin "27") (pinfunction "PA28_27") (pintype "bidirectional"))
    )
  )
)
